# 6_Layer_sample.net
KiCad netlist of a schematic drawn in EAGLE
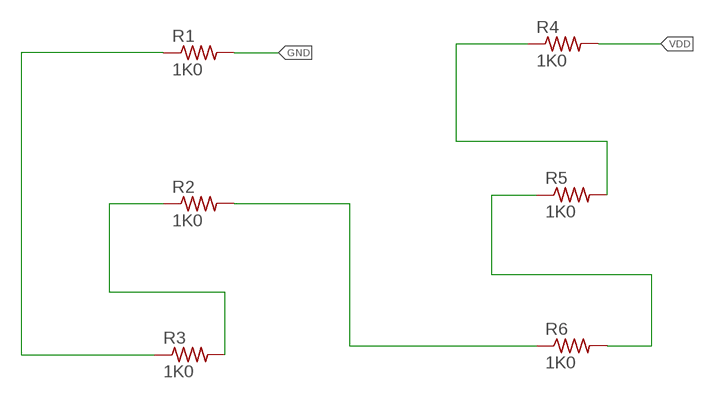
[diagram p0: schematic, sheet 1]

(export (version "E")
  (design (tool "Eeschema 10.0.6"))
  (components
    (comp (ref "R1")
      (value "1K0")
      (footprint "eagle-import:0402")
      (fields (field (name "PARTNO") "CRG0402J1K0"))
      (libsource (lib "eagle-import") (part "R_0402_1K0"))
    )
    (comp (ref "R2")
      (value "1K0")
      (footprint "eagle-import:0402")
      (fields (field (name "PARTNO") "CRG0402J1K0"))
      (libsource (lib "eagle-import") (part "R_0402_1K0"))
    )
    (comp (ref "R3")
      (value "1K0")
      (footprint "eagle-import:0402")
      (fields (field (name "PARTNO") "CRG0402J1K0"))
      (libsource (lib "eagle-import") (part "R_0402_1K0"))
    )
    (comp (ref "R4")
      (value "1K0")
      (footprint "eagle-import:0402")
      (fields (field (name "PARTNO") "CRG0402J1K0"))
      (libsource (lib "eagle-import") (part "R_0402_1K0"))
    )
    (comp (ref "R5")
      (value "1K0")
      (footprint "eagle-import:0402")
      (fields (field (name "PARTNO") "CRG0402J1K0"))
      (libsource (lib "eagle-import") (part "R_0402_1K0"))
    )
    (comp (ref "R6")
      (value "1K0")
      (footprint "eagle-import:0402")
      (fields (field (name "PARTNO") "CRG0402J1K0"))
      (libsource (lib "eagle-import") (part "R_0402_1K0"))
    )
  )
  (nets
    (net (code "1") (name "GND") (class "Default")
      (node (ref "R1") (pin "P$2") (pinfunction "2_P$2") (pintype "passive"))
    )
    (net (code "2") (name "Net-(R1-1)") (class "Default")
      (node (ref "R1") (pin "P$1") (pinfunction "1_P$1") (pintype "passive"))
      (node (ref "R3") (pin "P$1") (pinfunction "1_P$1") (pintype "passive"))
    )
    (net (code "3") (name "Net-(R2-1)") (class "Default")
      (node (ref "R2") (pin "P$1") (pinfunction "1_P$1") (pintype "passive"))
      (node (ref "R3") (pin "P$2") (pinfunction "2_P$2") (pintype "passive"))
    )
    (net (code "4") (name "Net-(R2-2)") (class "Default")
      (node (ref "R2") (pin "P$2") (pinfunction "2_P$2") (pintype "passive"))
      (node (ref "R6") (pin "P$1") (pinfunction "1_P$1") (pintype "passive"))
    )
    (net (code "5") (name "Net-(R4-1)") (class "Default")
      (node (ref "R4") (pin "P$1") (pinfunction "1_P$1") (pintype "passive"))
      (node (ref "R5") (pin "P$2") (pinfunction "2_P$2") (pintype "passive"))
    )
    (net (code "6") (name "Net-(R5-1)") (class "Default")
      (node (ref "R5") (pin "P$1") (pinfunction "1_P$1") (pintype "passive"))
      (node (ref "R6") (pin "P$2") (pinfunction "2_P$2") (pintype "passive"))
    )
    (net (code "7") (name "VDD") (class "Default")
      (node (ref "R4") (pin "P$2") (pinfunction "2_P$2") (pintype "passive"))
    )
  )
)
